# Electronicsmb.net
KiCad netlist of a schematic drawn in EAGLE
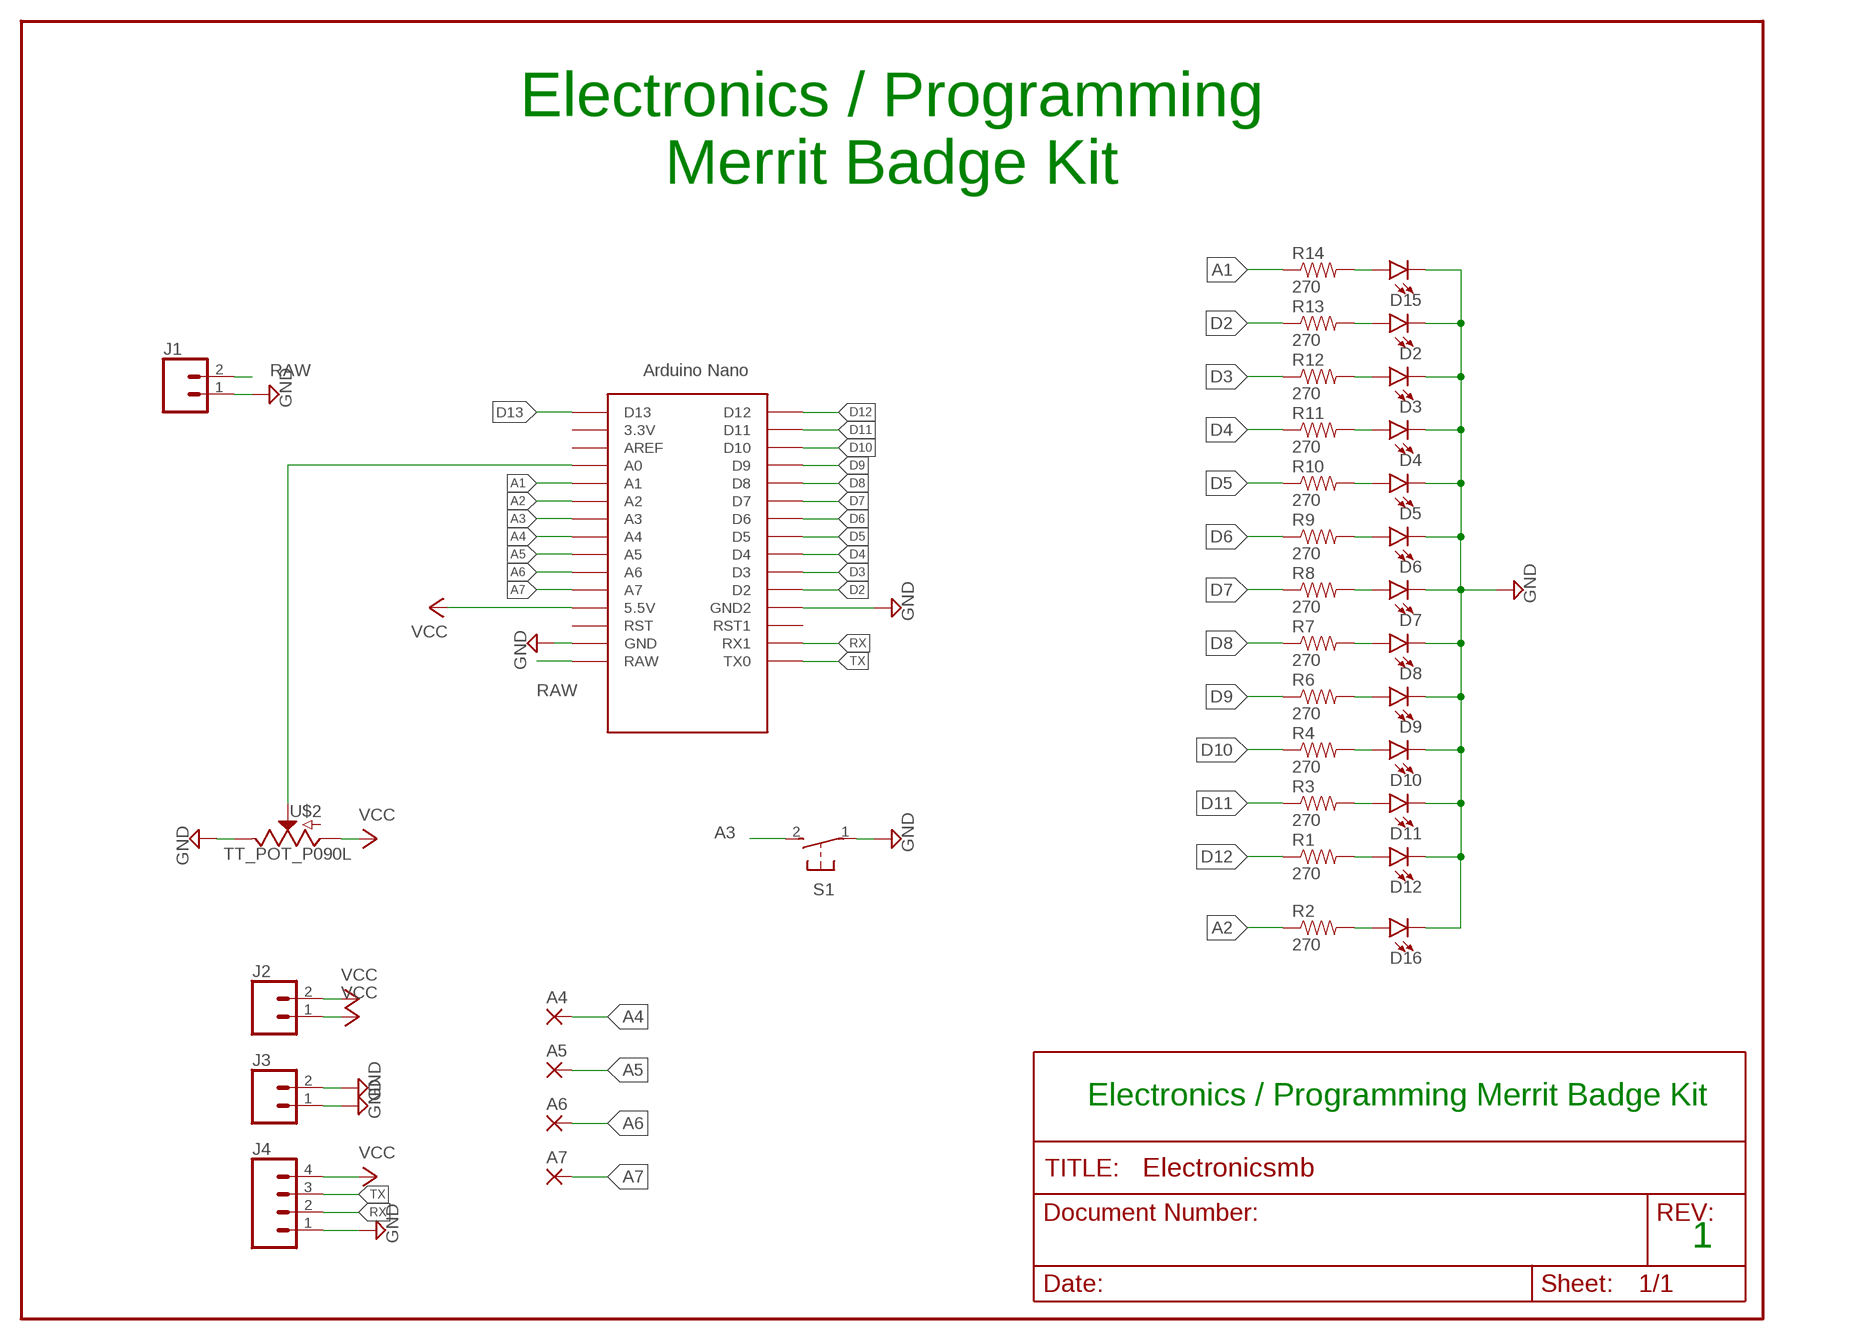
[diagram p0: schematic, sheet 1]

(export (version "E")
  (design (tool "Eeschema 10.0.6"))
  (components
    (comp (ref "A4")
      (value "2,54/1,0")
      (footprint "eagle-import:2,54_1,0")
      (libsource (lib "eagle-import") (part "2,54/1,0"))
    )
    (comp (ref "A5")
      (value "2,54/1,0")
      (footprint "eagle-import:2,54_1,0")
      (libsource (lib "eagle-import") (part "2,54/1,0"))
    )
    (comp (ref "A6")
      (value "2,54/1,0")
      (footprint "eagle-import:2,54_1,0")
      (libsource (lib "eagle-import") (part "2,54/1,0"))
    )
    (comp (ref "A7")
      (value "2,54/1,0")
      (footprint "eagle-import:2,54_1,0")
      (libsource (lib "eagle-import") (part "2,54/1,0"))
    )
    (comp (ref "D2")
      (value "LED5MM")
      (footprint "eagle-import:LED_5MM")
      (libsource (lib "eagle-import") (part "LED5MM"))
    )
    (comp (ref "D3")
      (value "LED5MM")
      (footprint "eagle-import:LED_5MM")
      (libsource (lib "eagle-import") (part "LED5MM"))
    )
    (comp (ref "D4")
      (value "LED5MM")
      (footprint "eagle-import:LED_5MM")
      (libsource (lib "eagle-import") (part "LED5MM"))
    )
    (comp (ref "D5")
      (value "LED5MM")
      (footprint "eagle-import:LED_5MM")
      (libsource (lib "eagle-import") (part "LED5MM"))
    )
    (comp (ref "D6")
      (value "LED5MM")
      (footprint "eagle-import:LED_5MM")
      (libsource (lib "eagle-import") (part "LED5MM"))
    )
    (comp (ref "D7")
      (value "LED5MM")
      (footprint "eagle-import:LED_5MM")
      (libsource (lib "eagle-import") (part "LED5MM"))
    )
    (comp (ref "D8")
      (value "LED5MM")
      (footprint "eagle-import:LED_5MM")
      (libsource (lib "eagle-import") (part "LED5MM"))
    )
    (comp (ref "D9")
      (value "LED5MM")
      (footprint "eagle-import:LED_5MM")
      (libsource (lib "eagle-import") (part "LED5MM"))
    )
    (comp (ref "D10")
      (value "LED5MM")
      (footprint "eagle-import:LED_5MM")
      (libsource (lib "eagle-import") (part "LED5MM"))
    )
    (comp (ref "D11")
      (value "LED5MM")
      (footprint "eagle-import:LED_5MM")
      (libsource (lib "eagle-import") (part "LED5MM"))
    )
    (comp (ref "D12")
      (value "LED5MM")
      (footprint "eagle-import:LED_5MM")
      (libsource (lib "eagle-import") (part "LED5MM"))
    )
    (comp (ref "D15")
      (value "LED5MM")
      (footprint "eagle-import:LED_5MM")
      (libsource (lib "eagle-import") (part "LED5MM"))
    )
    (comp (ref "D16")
      (value "LED5MM")
      (footprint "eagle-import:LED_5MM")
      (libsource (lib "eagle-import") (part "LED5MM"))
    )
    (comp (ref "J1")
      (value "CONN_02")
      (footprint "eagle-import:1X02")
      (libsource (lib "eagle-import") (part "CONN_02"))
    )
    (comp (ref "J2")
      (value "CONN_02")
      (footprint "eagle-import:1X02")
      (libsource (lib "eagle-import") (part "CONN_02"))
    )
    (comp (ref "J3")
      (value "CONN_02")
      (footprint "eagle-import:1X02")
      (libsource (lib "eagle-import") (part "CONN_02"))
    )
    (comp (ref "J4")
      (value "CONN_04")
      (footprint "eagle-import:1X04")
      (libsource (lib "eagle-import") (part "CONN_04"))
    )
    (comp (ref "R1")
      (value "270")
      (footprint "eagle-import:AXIAL-0.4")
      (libsource (lib "eagle-import") (part "RESISTORPTH-1/4W"))
    )
    (comp (ref "R2")
      (value "270")
      (footprint "eagle-import:AXIAL-0.4")
      (libsource (lib "eagle-import") (part "RESISTORPTH-1/4W"))
    )
    (comp (ref "R3")
      (value "270")
      (footprint "eagle-import:AXIAL-0.4")
      (libsource (lib "eagle-import") (part "RESISTORPTH-1/4W"))
    )
    (comp (ref "R4")
      (value "270")
      (footprint "eagle-import:AXIAL-0.4")
      (libsource (lib "eagle-import") (part "RESISTORPTH-1/4W"))
    )
    (comp (ref "R6")
      (value "270")
      (footprint "eagle-import:AXIAL-0.4")
      (libsource (lib "eagle-import") (part "RESISTORPTH-1/4W"))
    )
    (comp (ref "R7")
      (value "270")
      (footprint "eagle-import:AXIAL-0.4")
      (libsource (lib "eagle-import") (part "RESISTORPTH-1/4W"))
    )
    (comp (ref "R8")
      (value "270")
      (footprint "eagle-import:AXIAL-0.4")
      (libsource (lib "eagle-import") (part "RESISTORPTH-1/4W"))
    )
    (comp (ref "R9")
      (value "270")
      (footprint "eagle-import:AXIAL-0.4")
      (libsource (lib "eagle-import") (part "RESISTORPTH-1/4W"))
    )
    (comp (ref "R10")
      (value "270")
      (footprint "eagle-import:AXIAL-0.4")
      (libsource (lib "eagle-import") (part "RESISTORPTH-1/4W"))
    )
    (comp (ref "R11")
      (value "270")
      (footprint "eagle-import:AXIAL-0.4")
      (libsource (lib "eagle-import") (part "RESISTORPTH-1/4W"))
    )
    (comp (ref "R12")
      (value "270")
      (footprint "eagle-import:AXIAL-0.4")
      (libsource (lib "eagle-import") (part "RESISTORPTH-1/4W"))
    )
    (comp (ref "R13")
      (value "270")
      (footprint "eagle-import:AXIAL-0.4")
      (libsource (lib "eagle-import") (part "RESISTORPTH-1/4W"))
    )
    (comp (ref "R14")
      (value "270")
      (footprint "eagle-import:AXIAL-0.4")
      (libsource (lib "eagle-import") (part "RESISTORPTH-1/4W"))
    )
    (comp (ref "S1")
      (value "31-XX")
      (footprint "eagle-import:B3F-31XX")
      (fields (field (name "MPN") "B3F-3100"))
      (libsource (lib "eagle-import") (part "31-XX"))
    )
    (comp (ref "U$1")
      (value "NANO")
      (footprint "eagle-import:NANO")
      (libsource (lib "eagle-import") (part "NANO"))
    )
    (comp (ref "U$2")
      (value "TT_POT_P090L")
      (footprint "eagle-import:TT_POT")
      (libsource (lib "eagle-import") (part "TT_POT_P090L"))
    )
  )
  (nets
    (net (code "1") (name "/RAW") (class "Default")
      (node (ref "J1") (pin "2") (pinfunction "2_2") (pintype "passive"))
      (node (ref "U$1") (pin "RAW") (pinfunction "RAW_RAW") (pintype "bidirectional"))
    )
    (net (code "2") (name "A1") (class "Default")
      (node (ref "R14") (pin "P$1") (pinfunction "1_P$1") (pintype "passive"))
      (node (ref "U$1") (pin "A1") (pinfunction "A1_A1") (pintype "bidirectional"))
    )
    (net (code "3") (name "A2") (class "Default")
      (node (ref "R2") (pin "P$1") (pinfunction "1_P$1") (pintype "passive"))
      (node (ref "U$1") (pin "A2") (pinfunction "A2_A2") (pintype "bidirectional"))
    )
    (net (code "4") (name "A3") (class "Default")
      (node (ref "S1") (pin "2") (pinfunction "S_2") (pintype "passive"))
      (node (ref "U$1") (pin "A3") (pinfunction "A3_A3") (pintype "bidirectional"))
    )
    (net (code "5") (name "A4") (class "Default")
      (node (ref "A4") (pin "1") (pinfunction "P_1") (pintype "passive"))
      (node (ref "U$1") (pin "A4") (pinfunction "A4_A4") (pintype "bidirectional"))
    )
    (net (code "6") (name "A5") (class "Default")
      (node (ref "A5") (pin "1") (pinfunction "P_1") (pintype "passive"))
      (node (ref "U$1") (pin "A5") (pinfunction "A5_A5") (pintype "bidirectional"))
    )
    (net (code "7") (name "A6") (class "Default")
      (node (ref "A6") (pin "1") (pinfunction "P_1") (pintype "passive"))
      (node (ref "U$1") (pin "A6") (pinfunction "A6_A6") (pintype "bidirectional"))
    )
    (net (code "8") (name "A7") (class "Default")
      (node (ref "A7") (pin "1") (pinfunction "P_1") (pintype "passive"))
      (node (ref "U$1") (pin "A7") (pinfunction "A7_A7") (pintype "bidirectional"))
    )
    (net (code "9") (name "D2") (class "Default")
      (node (ref "R13") (pin "P$1") (pinfunction "1_P$1") (pintype "passive"))
      (node (ref "U$1") (pin "D2") (pinfunction "D2_D2") (pintype "bidirectional"))
    )
    (net (code "10") (name "D3") (class "Default")
      (node (ref "R12") (pin "P$1") (pinfunction "1_P$1") (pintype "passive"))
      (node (ref "U$1") (pin "D3") (pinfunction "D3_D3") (pintype "bidirectional"))
    )
    (net (code "11") (name "D4") (class "Default")
      (node (ref "R11") (pin "P$1") (pinfunction "1_P$1") (pintype "passive"))
      (node (ref "U$1") (pin "D4") (pinfunction "D4_D4") (pintype "bidirectional"))
    )
    (net (code "12") (name "D5") (class "Default")
      (node (ref "R10") (pin "P$1") (pinfunction "1_P$1") (pintype "passive"))
      (node (ref "U$1") (pin "D5") (pinfunction "D5_D5") (pintype "bidirectional"))
    )
    (net (code "13") (name "D6") (class "Default")
      (node (ref "R9") (pin "P$1") (pinfunction "1_P$1") (pintype "passive"))
      (node (ref "U$1") (pin "D6") (pinfunction "D6_D6") (pintype "bidirectional"))
    )
    (net (code "14") (name "D7") (class "Default")
      (node (ref "R8") (pin "P$1") (pinfunction "1_P$1") (pintype "passive"))
      (node (ref "U$1") (pin "D7") (pinfunction "D7_D7") (pintype "bidirectional"))
    )
    (net (code "15") (name "D8") (class "Default")
      (node (ref "R7") (pin "P$1") (pinfunction "1_P$1") (pintype "passive"))
      (node (ref "U$1") (pin "D8") (pinfunction "D8_D8") (pintype "bidirectional"))
    )
    (net (code "16") (name "D9") (class "Default")
      (node (ref "R6") (pin "P$1") (pinfunction "1_P$1") (pintype "passive"))
      (node (ref "U$1") (pin "D9") (pinfunction "D9_D9") (pintype "bidirectional"))
    )
    (net (code "17") (name "D10") (class "Default")
      (node (ref "R4") (pin "P$1") (pinfunction "1_P$1") (pintype "passive"))
      (node (ref "U$1") (pin "D10") (pinfunction "D10_D10") (pintype "bidirectional"))
    )
    (net (code "18") (name "D11") (class "Default")
      (node (ref "R3") (pin "P$1") (pinfunction "1_P$1") (pintype "passive"))
      (node (ref "U$1") (pin "D11") (pinfunction "D11_D11") (pintype "bidirectional"))
    )
    (net (code "19") (name "D12") (class "Default")
      (node (ref "R1") (pin "P$1") (pinfunction "1_P$1") (pintype "passive"))
      (node (ref "U$1") (pin "D12") (pinfunction "D12_D12") (pintype "bidirectional"))
    )
    (net (code "20") (name "D13") (class "Default")
      (node (ref "U$1") (pin "D13") (pinfunction "D13_D13") (pintype "bidirectional"))
    )
    (net (code "21") (name "GND") (class "Default")
      (node (ref "D10") (pin "K") (pinfunction "C_K") (pintype "passive"))
      (node (ref "D11") (pin "K") (pinfunction "C_K") (pintype "passive"))
      (node (ref "D12") (pin "K") (pinfunction "C_K") (pintype "passive"))
      (node (ref "D15") (pin "K") (pinfunction "C_K") (pintype "passive"))
      (node (ref "D16") (pin "K") (pinfunction "C_K") (pintype "passive"))
      (node (ref "D2") (pin "K") (pinfunction "C_K") (pintype "passive"))
      (node (ref "D3") (pin "K") (pinfunction "C_K") (pintype "passive"))
      (node (ref "D4") (pin "K") (pinfunction "C_K") (pintype "passive"))
      (node (ref "D5") (pin "K") (pinfunction "C_K") (pintype "passive"))
      (node (ref "D6") (pin "K") (pinfunction "C_K") (pintype "passive"))
      (node (ref "D7") (pin "K") (pinfunction "C_K") (pintype "passive"))
      (node (ref "D8") (pin "K") (pinfunction "C_K") (pintype "passive"))
      (node (ref "D9") (pin "K") (pinfunction "C_K") (pintype "passive"))
      (node (ref "J1") (pin "1") (pinfunction "1_1") (pintype "passive"))
      (node (ref "J3") (pin "1") (pinfunction "1_1") (pintype "passive"))
      (node (ref "J3") (pin "2") (pinfunction "2_2") (pintype "passive"))
      (node (ref "J4") (pin "1") (pinfunction "1_1") (pintype "passive"))
      (node (ref "S1") (pin "1") (pinfunction "P_1") (pintype "passive"))
      (node (ref "U$1") (pin "GND") (pinfunction "GND_GND") (pintype "bidirectional"))
      (node (ref "U$1") (pin "GND1") (pinfunction "GND2_GND1") (pintype "bidirectional"))
      (node (ref "U$2") (pin "P$3") (pinfunction "E_P$3") (pintype "passive"))
    )
    (net (code "22") (name "Net-(R1-2)") (class "Default")
      (node (ref "D12") (pin "A") (pinfunction "A_A") (pintype "passive"))
      (node (ref "R1") (pin "P$2") (pinfunction "2_P$2") (pintype "passive"))
    )
    (net (code "23") (name "Net-(R2-2)") (class "Default")
      (node (ref "D16") (pin "A") (pinfunction "A_A") (pintype "passive"))
      (node (ref "R2") (pin "P$2") (pinfunction "2_P$2") (pintype "passive"))
    )
    (net (code "24") (name "Net-(R3-2)") (class "Default")
      (node (ref "D11") (pin "A") (pinfunction "A_A") (pintype "passive"))
      (node (ref "R3") (pin "P$2") (pinfunction "2_P$2") (pintype "passive"))
    )
    (net (code "25") (name "Net-(R4-2)") (class "Default")
      (node (ref "D10") (pin "A") (pinfunction "A_A") (pintype "passive"))
      (node (ref "R4") (pin "P$2") (pinfunction "2_P$2") (pintype "passive"))
    )
    (net (code "26") (name "Net-(R6-2)") (class "Default")
      (node (ref "D9") (pin "A") (pinfunction "A_A") (pintype "passive"))
      (node (ref "R6") (pin "P$2") (pinfunction "2_P$2") (pintype "passive"))
    )
    (net (code "27") (name "Net-(R7-2)") (class "Default")
      (node (ref "D8") (pin "A") (pinfunction "A_A") (pintype "passive"))
      (node (ref "R7") (pin "P$2") (pinfunction "2_P$2") (pintype "passive"))
    )
    (net (code "28") (name "Net-(R8-2)") (class "Default")
      (node (ref "D7") (pin "A") (pinfunction "A_A") (pintype "passive"))
      (node (ref "R8") (pin "P$2") (pinfunction "2_P$2") (pintype "passive"))
    )
    (net (code "29") (name "Net-(R9-2)") (class "Default")
      (node (ref "D6") (pin "A") (pinfunction "A_A") (pintype "passive"))
      (node (ref "R9") (pin "P$2") (pinfunction "2_P$2") (pintype "passive"))
    )
    (net (code "30") (name "Net-(R10-2)") (class "Default")
      (node (ref "D5") (pin "A") (pinfunction "A_A") (pintype "passive"))
      (node (ref "R10") (pin "P$2") (pinfunction "2_P$2") (pintype "passive"))
    )
    (net (code "31") (name "Net-(R11-2)") (class "Default")
      (node (ref "D4") (pin "A") (pinfunction "A_A") (pintype "passive"))
      (node (ref "R11") (pin "P$2") (pinfunction "2_P$2") (pintype "passive"))
    )
    (net (code "32") (name "Net-(R12-2)") (class "Default")
      (node (ref "D3") (pin "A") (pinfunction "A_A") (pintype "passive"))
      (node (ref "R12") (pin "P$2") (pinfunction "2_P$2") (pintype "passive"))
    )
    (net (code "33") (name "Net-(R13-2)") (class "Default")
      (node (ref "D2") (pin "A") (pinfunction "A_A") (pintype "passive"))
      (node (ref "R13") (pin "P$2") (pinfunction "2_P$2") (pintype "passive"))
    )
    (net (code "34") (name "Net-(R14-2)") (class "Default")
      (node (ref "D15") (pin "A") (pinfunction "A_A") (pintype "passive"))
      (node (ref "R14") (pin "P$2") (pinfunction "2_P$2") (pintype "passive"))
    )
    (net (code "35") (name "Net-(U$2-S)") (class "Default")
      (node (ref "U$1") (pin "A0") (pinfunction "A0_A0") (pintype "bidirectional"))
      (node (ref "U$2") (pin "P$2") (pinfunction "S_P$2") (pintype "passive"))
    )
    (net (code "36") (name "RX") (class "Default")
      (node (ref "J4") (pin "2") (pinfunction "2_2") (pintype "passive"))
      (node (ref "U$1") (pin "RX1") (pinfunction "RX1_RX1") (pintype "bidirectional"))
    )
    (net (code "37") (name "TX") (class "Default")
      (node (ref "J4") (pin "3") (pinfunction "3_3") (pintype "passive"))
      (node (ref "U$1") (pin "TX0") (pinfunction "TX0_TX0") (pintype "bidirectional"))
    )
    (net (code "38") (name "VCC") (class "Default")
      (node (ref "J2") (pin "1") (pinfunction "1_1") (pintype "passive"))
      (node (ref "J2") (pin "2") (pinfunction "2_2") (pintype "passive"))
      (node (ref "J4") (pin "4") (pinfunction "4_4") (pintype "passive"))
      (node (ref "U$1") (pin "5V") (pinfunction "5.5V_5V") (pintype "bidirectional"))
      (node (ref "U$2") (pin "P$1") (pinfunction "A_P$1") (pintype "passive"))
    )
    (net (code "39") (name "unconnected-(U$1-Pad3.3V)") (class "Default")
      (node (ref "U$1") (pin "3.3V") (pinfunction "3.3V_3.3V") (pintype "bidirectional"))
    )
    (net (code "40") (name "unconnected-(U$1-PadAREF)") (class "Default")
      (node (ref "U$1") (pin "AREF") (pinfunction "AREF_AREF") (pintype "bidirectional"))
    )
    (net (code "41") (name "unconnected-(U$1-PadICSP1)") (class "Default")
      (node (ref "U$1") (pin "ICSP1") (pinfunction "ICSP1_ICSP1") (pintype "bidirectional"))
    )
    (net (code "42") (name "unconnected-(U$1-PadICSP2)") (class "Default")
      (node (ref "U$1") (pin "ICSP2") (pinfunction "ICSP2_ICSP2") (pintype "bidirectional"))
    )
    (net (code "43") (name "unconnected-(U$1-PadICSP3)") (class "Default")
      (node (ref "U$1") (pin "ICSP3") (pinfunction "ICSP3_ICSP3") (pintype "bidirectional"))
    )
    (net (code "44") (name "unconnected-(U$1-PadICSP4)") (class "Default")
      (node (ref "U$1") (pin "ICSP4") (pinfunction "ICSP4_ICSP4") (pintype "bidirectional"))
    )
    (net (code "45") (name "unconnected-(U$1-PadICSP5)") (class "Default")
      (node (ref "U$1") (pin "ICSP5") (pinfunction "ICSP5_ICSP5") (pintype "bidirectional"))
    )
    (net (code "46") (name "unconnected-(U$1-PadICSP6)") (class "Default")
      (node (ref "U$1") (pin "ICSP6") (pinfunction "ICSP6_ICSP6") (pintype "bidirectional"))
    )
    (net (code "47") (name "unconnected-(U$1-PadRST)") (class "Default")
      (node (ref "U$1") (pin "RST") (pinfunction "RST_RST") (pintype "bidirectional"))
    )
    (net (code "48") (name "unconnected-(U$1-PadRST1)") (class "Default")
      (node (ref "U$1") (pin "RST1") (pinfunction "RST1_RST1") (pintype "bidirectional"))
    )
  )
)
